# mikrophonie_2023.net
KiCad netlist of a schematic drawn in EAGLE
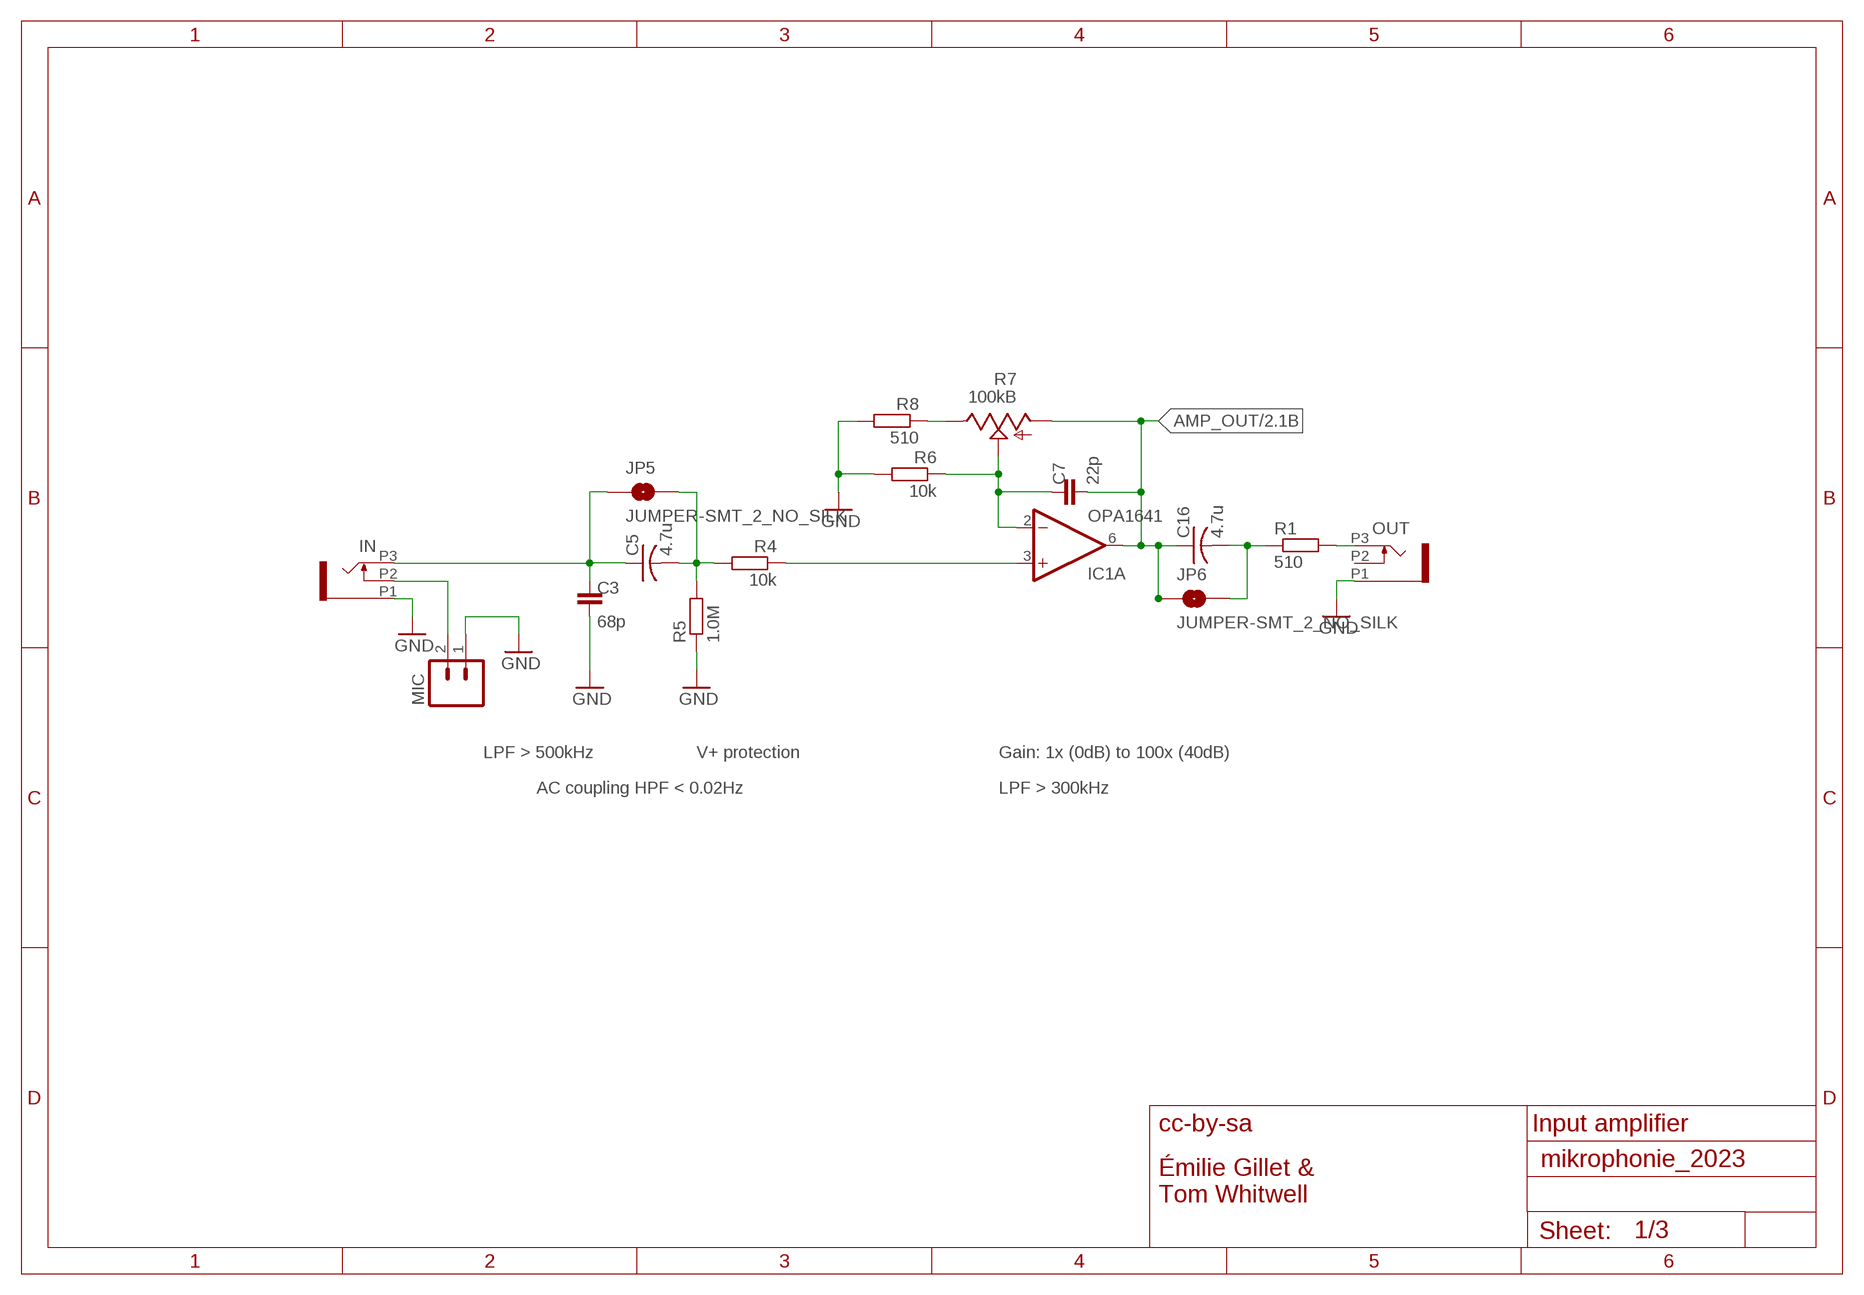
[diagram p0: schematic, sheet 1]
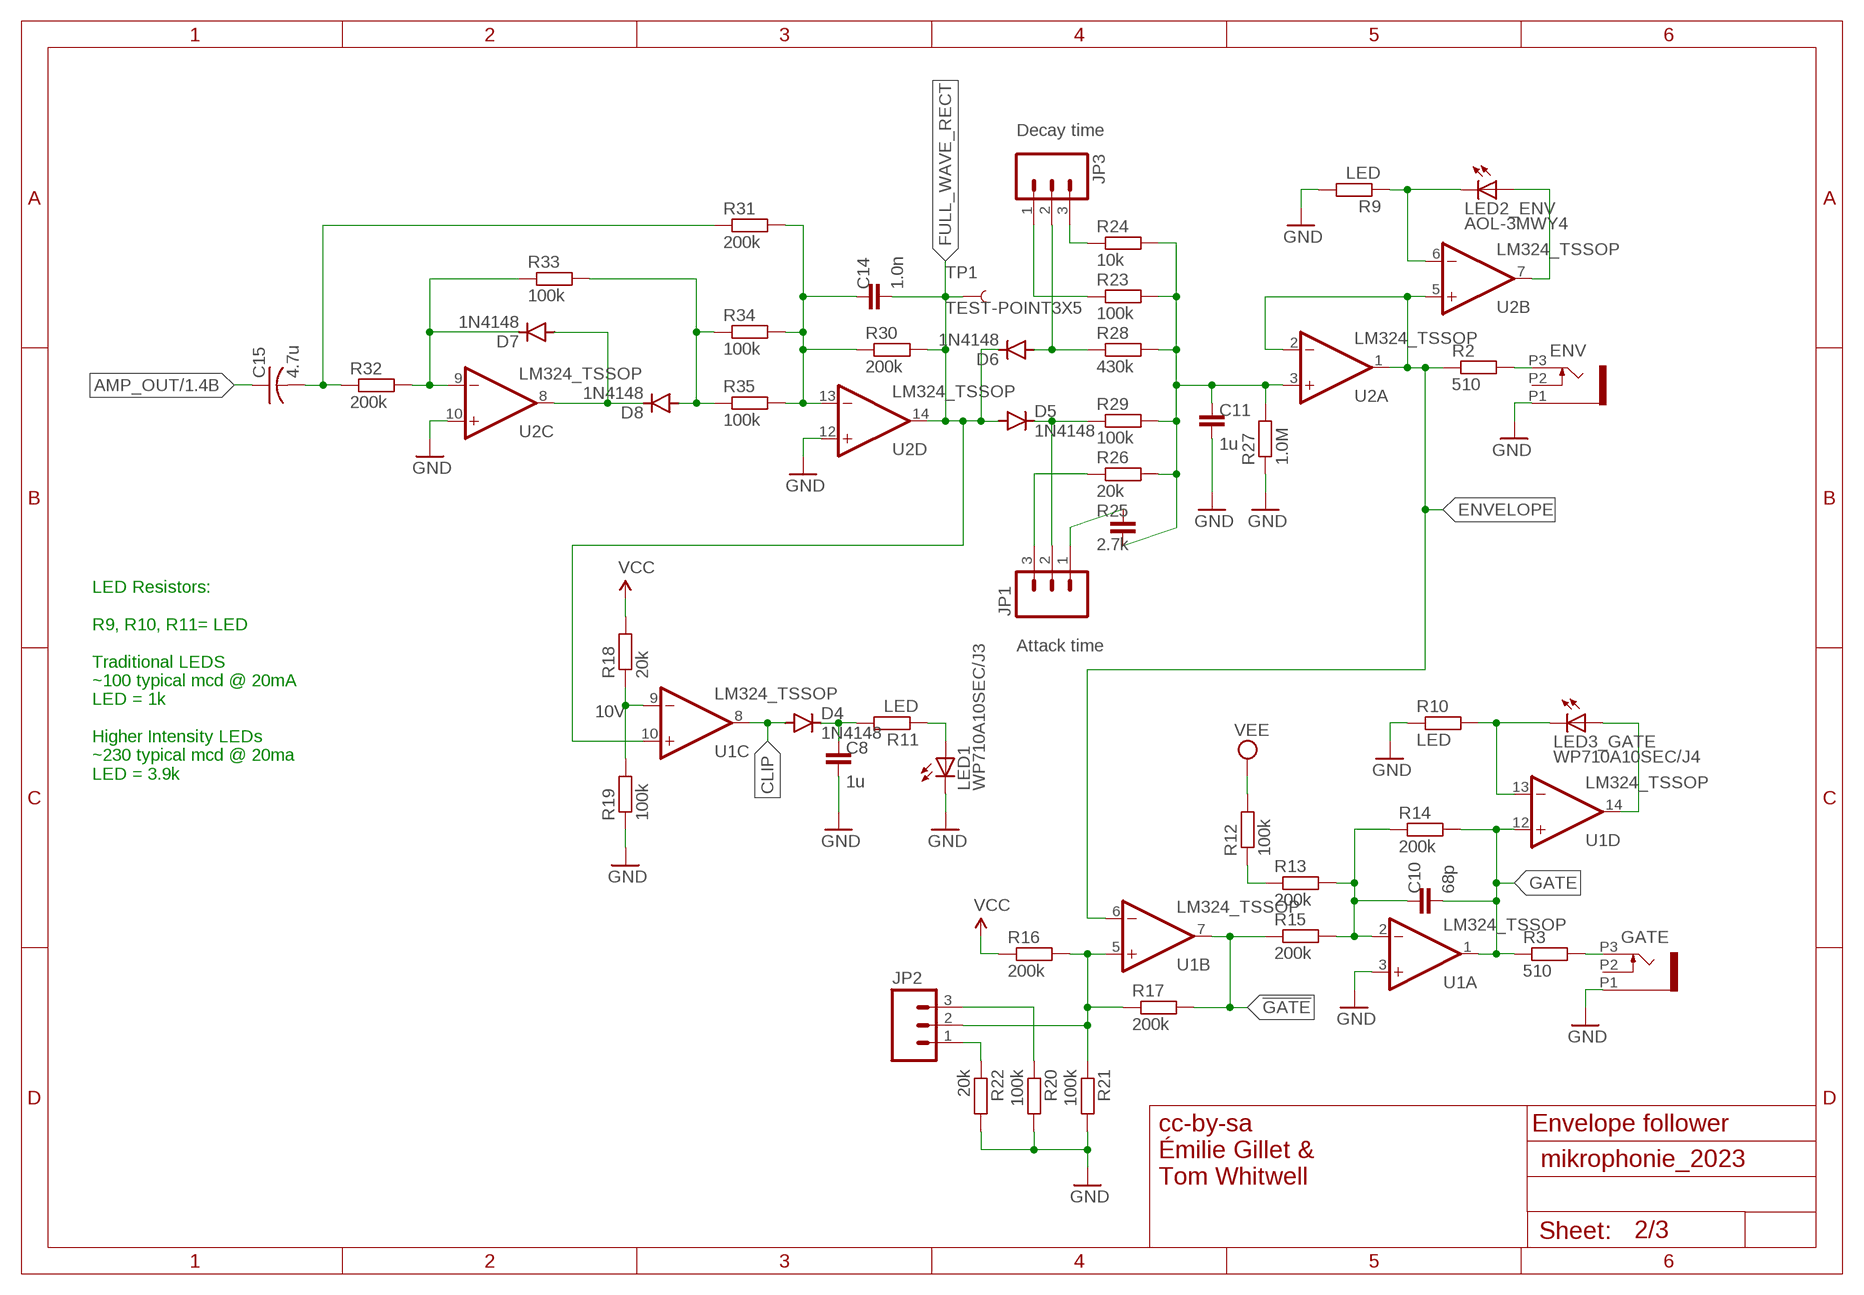
[diagram p1: schematic, sheet 2]
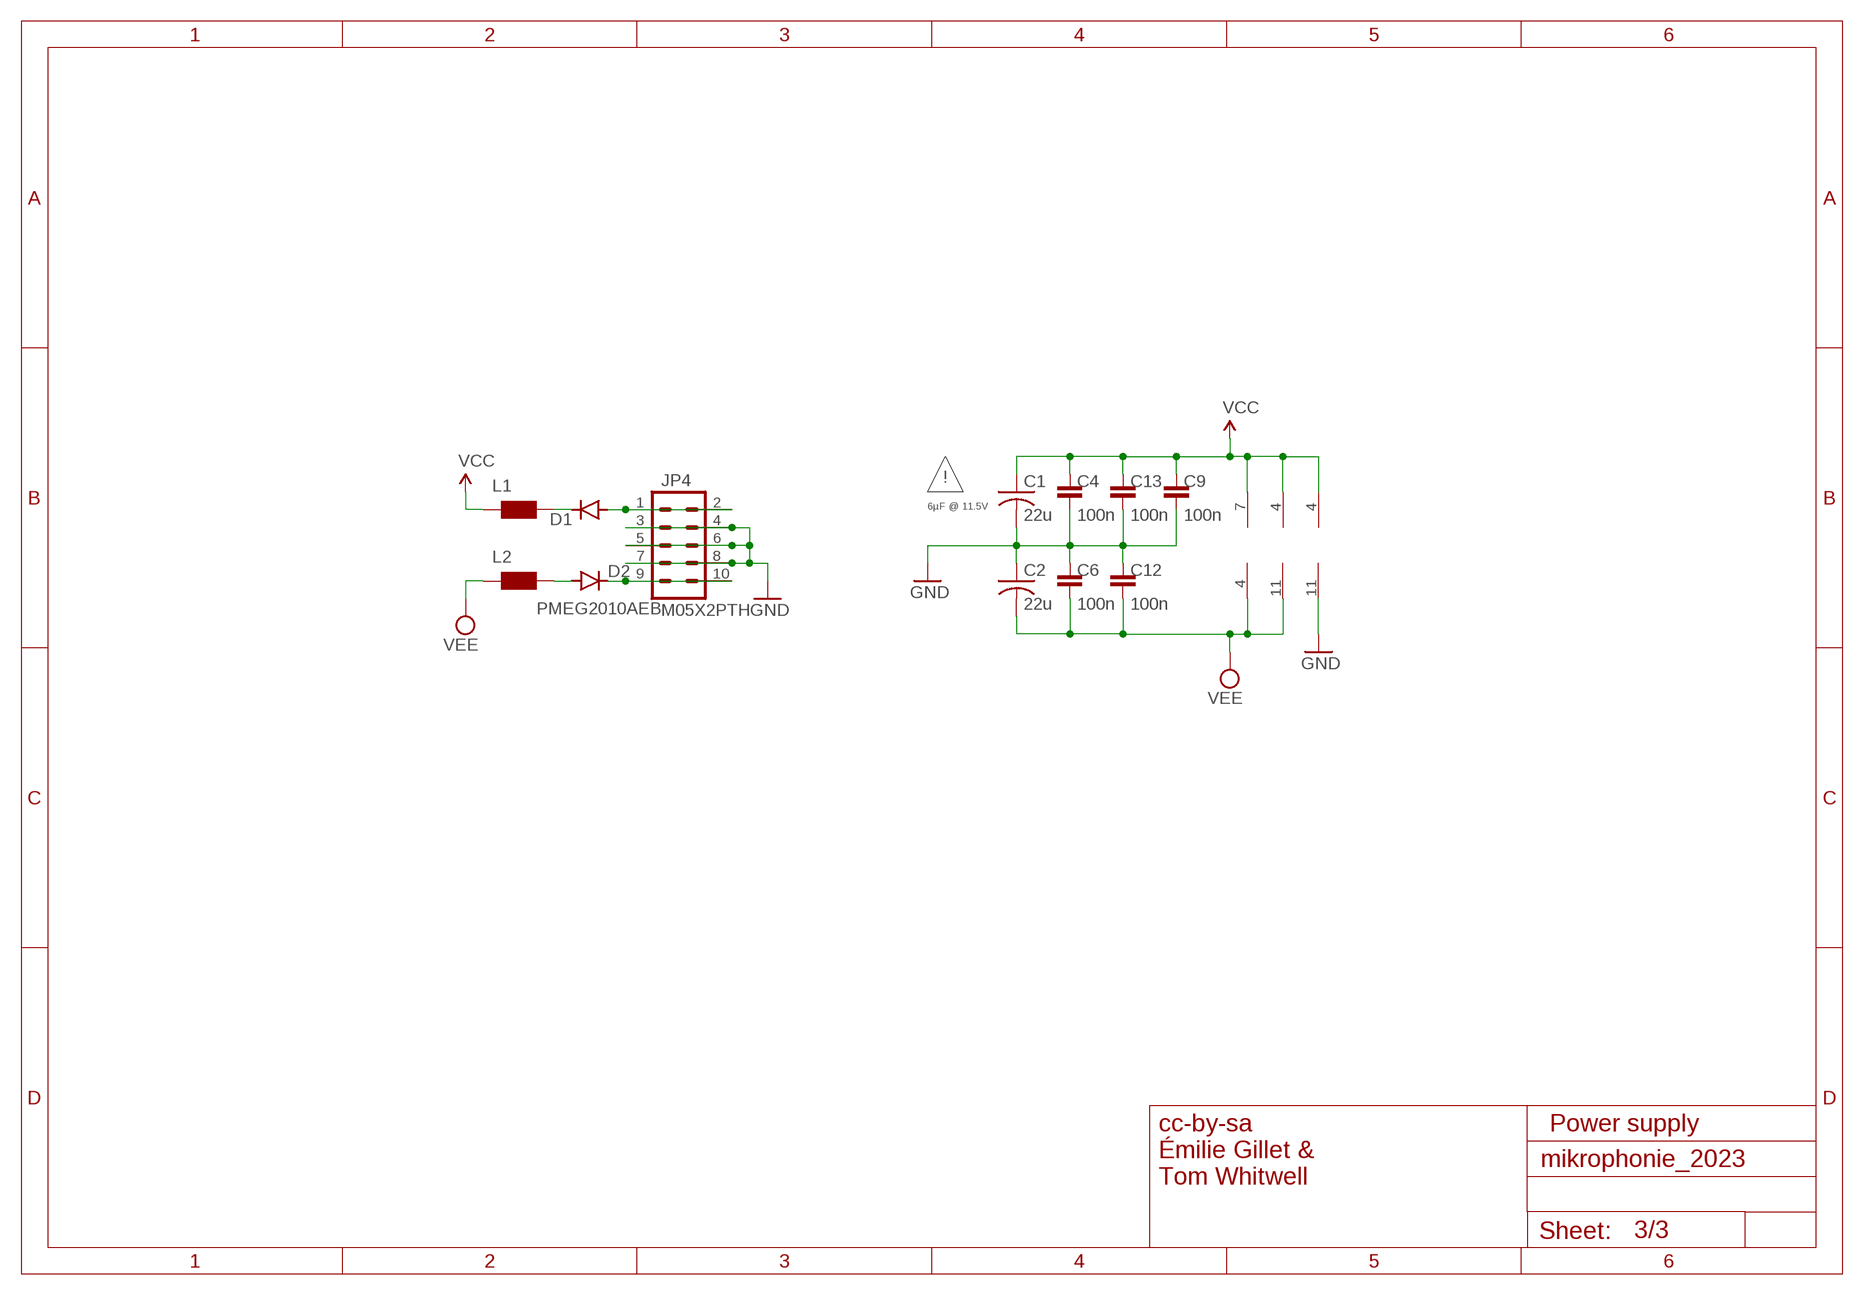
[diagram p2: schematic, sheet 3]

(export (version "E")
  (design (tool "Eeschema 10.0.6"))
  (components
    (comp (ref "C8")
      (value "1u")
      (footprint "eagle-import:C0402-90")
      (libsource (lib "eagle-import") (part "CAPACITOR-90"))
    )
    (comp (ref "C10")
      (value "68p")
      (footprint "eagle-import:C0402-90")
      (libsource (lib "eagle-import") (part "CAPACITOR-90"))
    )
    (comp (ref "C11")
      (value "1u")
      (footprint "eagle-import:C0402-90")
      (libsource (lib "eagle-import") (part "CAPACITOR-90"))
    )
    (comp (ref "C14")
      (value "1.0n")
      (footprint "eagle-import:C0402-90")
      (libsource (lib "eagle-import") (part "CAPACITOR-90"))
    )
    (comp (ref "C15")
      (value "4.7u")
      (footprint "eagle-import:C0603")
      (libsource (lib "eagle-import") (part "C-USC0603"))
    )
    (comp (ref "D4")
      (value "1N4148")
      (footprint "eagle-import:SOD523")
      (libsource (lib "eagle-import") (part "DIODE-SOD523"))
    )
    (comp (ref "D5")
      (value "1N4148")
      (footprint "eagle-import:SOD523")
      (libsource (lib "eagle-import") (part "DIODE-SOD523"))
    )
    (comp (ref "D6")
      (value "1N4148")
      (footprint "eagle-import:SOD523")
      (libsource (lib "eagle-import") (part "DIODE-SOD523"))
    )
    (comp (ref "D7")
      (value "1N4148")
      (footprint "eagle-import:SOD523")
      (libsource (lib "eagle-import") (part "DIODE-SOD523"))
    )
    (comp (ref "D8")
      (value "1N4148")
      (footprint "eagle-import:SOD523")
      (libsource (lib "eagle-import") (part "DIODE-SOD523"))
    )
    (comp (ref "ENV")
      (value "PJ301_THONKICONN6")
      (footprint "eagle-import:WQP_PJ_301M6")
      (libsource (lib "eagle-import") (part "PJ301_THONKICONN6"))
    )
    (comp (ref "GATE")
      (value "PJ301_THONKICONN6")
      (footprint "eagle-import:WQP_PJ_301M6")
      (libsource (lib "eagle-import") (part "PJ301_THONKICONN6"))
    )
    (comp (ref "JP1")
      (value "M03PTH")
      (footprint "eagle-import:1X03")
      (libsource (lib "eagle-import") (part "M03PTH"))
    )
    (comp (ref "JP2")
      (value "M03PTH")
      (footprint "eagle-import:1X03")
      (libsource (lib "eagle-import") (part "M03PTH"))
    )
    (comp (ref "JP3")
      (value "M03PTH")
      (footprint "eagle-import:1X03")
      (libsource (lib "eagle-import") (part "M03PTH"))
    )
    (comp (ref "LED1")
      (value "WP710A10SEC/J3")
      (footprint "eagle-import:LED3MM")
      (libsource (lib "eagle-import") (part "LED3MM"))
    )
    (comp (ref "LED2_ENV")
      (value "AOL-3MWY4")
      (footprint "eagle-import:LED3MM")
      (libsource (lib "eagle-import") (part "LED3MM"))
    )
    (comp (ref "LED3_GATE")
      (value "WP710A10SEC/J4")
      (footprint "eagle-import:LED3MM")
      (libsource (lib "eagle-import") (part "LED3MM"))
    )
    (comp (ref "R2")
      (value "510")
      (footprint "eagle-import:C0402-90")
      (libsource (lib "eagle-import") (part "RESISTOR-0402_90"))
    )
    (comp (ref "R3")
      (value "510")
      (footprint "eagle-import:C0402-90")
      (libsource (lib "eagle-import") (part "RESISTOR-0402_90"))
    )
    (comp (ref "R9")
      (value "LED")
      (footprint "eagle-import:C0402-90")
      (libsource (lib "eagle-import") (part "RESISTOR-0402_90"))
    )
    (comp (ref "R10")
      (value "LED")
      (footprint "eagle-import:C0402-90")
      (libsource (lib "eagle-import") (part "RESISTOR-0402_90"))
    )
    (comp (ref "R11")
      (value "LED")
      (footprint "eagle-import:C0402-90")
      (libsource (lib "eagle-import") (part "RESISTOR-0402_90"))
    )
    (comp (ref "R12")
      (value "100k")
      (footprint "eagle-import:C0402-90")
      (libsource (lib "eagle-import") (part "RESISTOR-0402_90"))
    )
    (comp (ref "R13")
      (value "200k")
      (footprint "eagle-import:C0402-90")
      (libsource (lib "eagle-import") (part "RESISTOR-0402_90"))
    )
    (comp (ref "R14")
      (value "200k")
      (footprint "eagle-import:C0402-90")
      (libsource (lib "eagle-import") (part "RESISTOR-0402_90"))
    )
    (comp (ref "R15")
      (value "200k")
      (footprint "eagle-import:C0402-90")
      (libsource (lib "eagle-import") (part "RESISTOR-0402_90"))
    )
    (comp (ref "R16")
      (value "200k")
      (footprint "eagle-import:C0402-90")
      (libsource (lib "eagle-import") (part "RESISTOR-0402_90"))
    )
    (comp (ref "R17")
      (value "200k")
      (footprint "eagle-import:C0402-90")
      (libsource (lib "eagle-import") (part "RESISTOR-0402_90"))
    )
    (comp (ref "R18")
      (value "20k")
      (footprint "eagle-import:C0402-90")
      (libsource (lib "eagle-import") (part "RESISTOR-0402_90"))
    )
    (comp (ref "R19")
      (value "100k")
      (footprint "eagle-import:C0402-90")
      (libsource (lib "eagle-import") (part "RESISTOR-0402_90"))
    )
    (comp (ref "R20")
      (value "100k")
      (footprint "eagle-import:C0402-90")
      (libsource (lib "eagle-import") (part "RESISTOR-0402_90"))
    )
    (comp (ref "R21")
      (value "100k")
      (footprint "eagle-import:C0402-90")
      (libsource (lib "eagle-import") (part "RESISTOR-0402_90"))
    )
    (comp (ref "R22")
      (value "20k")
      (footprint "eagle-import:C0402-90")
      (libsource (lib "eagle-import") (part "RESISTOR-0402_90"))
    )
    (comp (ref "R23")
      (value "100k")
      (footprint "eagle-import:C0402-90")
      (libsource (lib "eagle-import") (part "RESISTOR-0402_90"))
    )
    (comp (ref "R24")
      (value "10k")
      (footprint "eagle-import:C0402-90")
      (libsource (lib "eagle-import") (part "RESISTOR-0402_90"))
    )
    (comp (ref "R25")
      (value "2.7k")
      (footprint "eagle-import:C0402-90")
      (libsource (lib "eagle-import") (part "CAPACITOR-90"))
    )
    (comp (ref "R26")
      (value "20k")
      (footprint "eagle-import:C0402-90")
      (libsource (lib "eagle-import") (part "RESISTOR-0402_90"))
    )
    (comp (ref "R27")
      (value "1.0M")
      (footprint "eagle-import:C0402-90")
      (libsource (lib "eagle-import") (part "RESISTOR-0402_90"))
    )
    (comp (ref "R28")
      (value "430k")
      (footprint "eagle-import:C0402-90")
      (libsource (lib "eagle-import") (part "RESISTOR-0402_90"))
    )
    (comp (ref "R29")
      (value "100k")
      (footprint "eagle-import:C0402-90")
      (libsource (lib "eagle-import") (part "RESISTOR-0402_90"))
    )
    (comp (ref "R30")
      (value "200k")
      (footprint "eagle-import:C0402-90")
      (libsource (lib "eagle-import") (part "RESISTOR-0402_90"))
    )
    (comp (ref "R31")
      (value "200k")
      (footprint "eagle-import:C0402-90")
      (libsource (lib "eagle-import") (part "RESISTOR-0402_90"))
    )
    (comp (ref "R32")
      (value "200k")
      (footprint "eagle-import:C0402-90")
      (libsource (lib "eagle-import") (part "RESISTOR-0402_90"))
    )
    (comp (ref "R33")
      (value "100k")
      (footprint "eagle-import:C0402-90")
      (libsource (lib "eagle-import") (part "RESISTOR-0402_90"))
    )
    (comp (ref "R34")
      (value "100k")
      (footprint "eagle-import:C0402-90")
      (libsource (lib "eagle-import") (part "RESISTOR-0402_90"))
    )
    (comp (ref "R35")
      (value "100k")
      (footprint "eagle-import:C0402-90")
      (libsource (lib "eagle-import") (part "RESISTOR-0402_90"))
    )
    (comp (ref "TP1")
      (value "TEST-POINT3X5")
      (footprint "eagle-import:PAD.03X.05")
      (libsource (lib "eagle-import") (part "TEST-POINT3X5"))
    )
    (comp (ref "U1")
      (value "LM324_TSSOP")
      (footprint "eagle-import:SOP65P640X120-14N")
      (fields (field (name "MPN") "MCP6004-I/ST"))
      (libsource (lib "eagle-import") (part "LM324_TSSOP"))
    )
    (comp (ref "U2")
      (value "LM324_TSSOP")
      (footprint "eagle-import:SOP65P640X120-14N")
      (fields (field (name "MPN") "MCP6004-I/ST"))
      (libsource (lib "eagle-import") (part "LM324_TSSOP"))
    )
    (comp (ref "C1")
      (value "22u")
      (footprint "eagle-import:C1206")
      (libsource (lib "eagle-import") (part "C-USC1206"))
    )
    (comp (ref "C2")
      (value "22u")
      (footprint "eagle-import:C1206")
      (libsource (lib "eagle-import") (part "C-USC1206"))
    )
    (comp (ref "C4")
      (value "100n")
      (footprint "eagle-import:C0402-90")
      (libsource (lib "eagle-import") (part "CAPACITOR-90"))
    )
    (comp (ref "C6")
      (value "100n")
      (footprint "eagle-import:C0402-90")
      (libsource (lib "eagle-import") (part "CAPACITOR-90"))
    )
    (comp (ref "C9")
      (value "100n")
      (footprint "eagle-import:C0402-90")
      (libsource (lib "eagle-import") (part "CAPACITOR-90"))
    )
    (comp (ref "C12")
      (value "100n")
      (footprint "eagle-import:C0402-90")
      (libsource (lib "eagle-import") (part "CAPACITOR-90"))
    )
    (comp (ref "C13")
      (value "100n")
      (footprint "eagle-import:C0402-90")
      (libsource (lib "eagle-import") (part "CAPACITOR-90"))
    )
    (comp (ref "D1")
      (value "PMEG2010AEB")
      (footprint "eagle-import:SOD523")
      (libsource (lib "eagle-import") (part "DIODE-SOD523"))
    )
    (comp (ref "D2")
      (value "PMEG2010AEB")
      (footprint "eagle-import:SOD523")
      (libsource (lib "eagle-import") (part "DIODE-SOD523"))
    )
    (comp (ref "IC1")
      (value "OPA1641")
      (footprint "eagle-import:MSOP8")
      (libsource (lib "eagle-import") (part "OPA1641"))
    )
    (comp (ref "JP4")
      (value "M05X2PTH")
      (footprint "eagle-import:AVR_ICSP")
      (libsource (lib "eagle-import") (part "M05X2PTH"))
    )
    (comp (ref "L1")
      (value "WE-CBF_0603")
      (footprint "eagle-import:0603")
      (libsource (lib "eagle-import") (part "WE-CBF_0603"))
    )
    (comp (ref "L2")
      (value "WE-CBF_0603")
      (footprint "eagle-import:0603")
      (libsource (lib "eagle-import") (part "WE-CBF_0603"))
    )
    (comp (ref "C3")
      (value "68p")
      (footprint "eagle-import:C0402-90")
      (libsource (lib "eagle-import") (part "CAPACITOR-90"))
    )
    (comp (ref "C5")
      (value "4.7u")
      (footprint "eagle-import:C0603")
      (libsource (lib "eagle-import") (part "C-USC0603"))
    )
    (comp (ref "C7")
      (value "22p")
      (footprint "eagle-import:C0402-90")
      (libsource (lib "eagle-import") (part "CAPACITOR-90"))
    )
    (comp (ref "C16")
      (value "4.7u")
      (footprint "eagle-import:C0603")
      (libsource (lib "eagle-import") (part "C-USC0603"))
    )
    (comp (ref "IN")
      (value "PJ301_THONKICONN6")
      (footprint "eagle-import:WQP_PJ_301M6")
      (libsource (lib "eagle-import") (part "PJ301_THONKICONN6"))
    )
    (comp (ref "JP5")
      (value "JUMPER-SMT_2_NO_SILK")
      (footprint "eagle-import:SMT-JUMPER_2_NO_SILK")
      (libsource (lib "eagle-import") (part "JUMPER-SMT_2_NO_SILK"))
    )
    (comp (ref "JP6")
      (value "JUMPER-SMT_2_NO_SILK")
      (footprint "eagle-import:SMT-JUMPER_2_NO_SILK")
      (libsource (lib "eagle-import") (part "JUMPER-SMT_2_NO_SILK"))
    )
    (comp (ref "MIC")
      (value "M02TINY")
      (footprint "eagle-import:1X02_TINY")
      (libsource (lib "eagle-import") (part "M02TINY"))
    )
    (comp (ref "OUT")
      (value "PJ301_THONKICONN6")
      (footprint "eagle-import:WQP_PJ_301M6")
      (libsource (lib "eagle-import") (part "PJ301_THONKICONN6"))
    )
    (comp (ref "R1")
      (value "510")
      (footprint "eagle-import:C0402-90")
      (libsource (lib "eagle-import") (part "RESISTOR-0402_90"))
    )
    (comp (ref "R4")
      (value "10k")
      (footprint "eagle-import:C0402-90")
      (libsource (lib "eagle-import") (part "RESISTOR-0402_90"))
    )
    (comp (ref "R5")
      (value "1.0M")
      (footprint "eagle-import:C0402-90")
      (libsource (lib "eagle-import") (part "RESISTOR-0402_90"))
    )
    (comp (ref "R6")
      (value "10k")
      (footprint "eagle-import:C0402-90")
      (libsource (lib "eagle-import") (part "RESISTOR-0402_90"))
    )
    (comp (ref "R7")
      (value "100kB")
      (footprint "eagle-import:ALPS_POT_VERTICAL_PS")
      (libsource (lib "eagle-import") (part "POT_USVERTICAL_PS"))
    )
    (comp (ref "R8")
      (value "510")
      (footprint "eagle-import:C0402-90")
      (libsource (lib "eagle-import") (part "RESISTOR-0402_90"))
    )
  )
  (nets
    (net (code "1") (name "AMP_OUT") (class "Default")
      (node (ref "C15") (pin "1") (pinfunction "1_1") (pintype "passive"))
      (node (ref "C16") (pin "1") (pinfunction "1_1") (pintype "passive"))
      (node (ref "C7") (pin "2") (pinfunction "2_2") (pintype "passive"))
      (node (ref "IC1") (pin "6") (pinfunction "OUT_6") (pintype "output"))
      (node (ref "JP6") (pin "1") (pinfunction "1_1") (pintype "passive"))
      (node (ref "R7") (pin "P$3") (pinfunction "A_P$3") (pintype "passive"))
    )
    (net (code "2") (name "CLIP") (class "Default")
      (node (ref "D4") (pin "A") (pinfunction "A_A") (pintype "passive"))
      (node (ref "U1") (pin "8") (pinfunction "OUT_8") (pintype "output"))
    )
    (net (code "3") (name "ENVELOPE") (class "Default")
      (node (ref "R2") (pin "1") (pinfunction "1_1") (pintype "passive"))
      (node (ref "U1") (pin "6") (pinfunction "-IN_6") (pintype "input"))
      (node (ref "U2") (pin "1") (pinfunction "OUT_1") (pintype "output"))
      (node (ref "U2") (pin "2") (pinfunction "-IN_2") (pintype "input"))
      (node (ref "U2") (pin "5") (pinfunction "+IN_5") (pintype "input"))
    )
    (net (code "4") (name "FULL_WAVE_RECT") (class "Default")
      (node (ref "C14") (pin "2") (pinfunction "2_2") (pintype "passive"))
      (node (ref "D5") (pin "A") (pinfunction "A_A") (pintype "passive"))
      (node (ref "D6") (pin "C") (pinfunction "C_C") (pintype "passive"))
      (node (ref "R30") (pin "2") (pinfunction "2_2") (pintype "passive"))
      (node (ref "TP1") (pin "P$1") (pinfunction "1_P$1") (pintype "bidirectional"))
      (node (ref "U1") (pin "10") (pinfunction "+IN_10") (pintype "input"))
      (node (ref "U2") (pin "14") (pinfunction "OUT_14") (pintype "output"))
    )
    (net (code "5") (name "GATE") (class "Default")
      (node (ref "C10") (pin "2") (pinfunction "2_2") (pintype "passive"))
      (node (ref "R14") (pin "2") (pinfunction "2_2") (pintype "passive"))
      (node (ref "R3") (pin "1") (pinfunction "1_1") (pintype "passive"))
      (node (ref "U1") (pin "1") (pinfunction "OUT_1") (pintype "output"))
      (node (ref "U1") (pin "12") (pinfunction "+IN_12") (pintype "input"))
    )
    (net (code "6") (name "GND") (class "Default")
      (node (ref "C1") (pin "2") (pinfunction "2_2") (pintype "passive"))
      (node (ref "C11") (pin "2") (pinfunction "2_2") (pintype "passive"))
      (node (ref "C12") (pin "1") (pinfunction "1_1") (pintype "passive"))
      (node (ref "C13") (pin "2") (pinfunction "2_2") (pintype "passive"))
      (node (ref "C2") (pin "1") (pinfunction "1_1") (pintype "passive"))
      (node (ref "C3") (pin "2") (pinfunction "2_2") (pintype "passive"))
      (node (ref "C4") (pin "2") (pinfunction "2_2") (pintype "passive"))
      (node (ref "C6") (pin "1") (pinfunction "1_1") (pintype "passive"))
      (node (ref "C8") (pin "2") (pinfunction "2_2") (pintype "passive"))
      (node (ref "C9") (pin "2") (pinfunction "2_2") (pintype "passive"))
      (node (ref "ENV") (pin "P1") (pinfunction "1_P1") (pintype "passive"))
      (node (ref "GATE") (pin "P1") (pinfunction "1_P1") (pintype "passive"))
      (node (ref "IN") (pin "P1") (pinfunction "1_P1") (pintype "passive"))
      (node (ref "JP4") (pin "3") (pinfunction "3_3") (pintype "passive"))
      (node (ref "JP4") (pin "4") (pinfunction "4_4") (pintype "passive"))
      (node (ref "JP4") (pin "5") (pinfunction "5_5") (pintype "passive"))
      (node (ref "JP4") (pin "6") (pinfunction "6_6") (pintype "passive"))
      (node (ref "JP4") (pin "7") (pinfunction "7_7") (pintype "passive"))
      (node (ref "JP4") (pin "8") (pinfunction "8_8") (pintype "passive"))
      (node (ref "LED1") (pin "K") (pinfunction "C_K") (pintype "passive"))
      (node (ref "MIC") (pin "1") (pinfunction "1_1") (pintype "passive"))
      (node (ref "OUT") (pin "P1") (pinfunction "1_P1") (pintype "passive"))
      (node (ref "R10") (pin "1") (pinfunction "1_1") (pintype "passive"))
      (node (ref "R19") (pin "1") (pinfunction "1_1") (pintype "passive"))
      (node (ref "R20") (pin "2") (pinfunction "2_2") (pintype "passive"))
      (node (ref "R21") (pin "2") (pinfunction "2_2") (pintype "passive"))
      (node (ref "R22") (pin "2") (pinfunction "2_2") (pintype "passive"))
      (node (ref "R27") (pin "1") (pinfunction "1_1") (pintype "passive"))
      (node (ref "R5") (pin "1") (pinfunction "1_1") (pintype "passive"))
      (node (ref "R6") (pin "2") (pinfunction "2_2") (pintype "passive"))
      (node (ref "R8") (pin "2") (pinfunction "2_2") (pintype "passive"))
      (node (ref "R9") (pin "2") (pinfunction "2_2") (pintype "passive"))
      (node (ref "U1") (pin "11") (pinfunction "V-_11") (pintype "power_in"))
      (node (ref "U1") (pin "3") (pinfunction "+IN_3") (pintype "input"))
      (node (ref "U2") (pin "10") (pinfunction "+IN_10") (pintype "input"))
      (node (ref "U2") (pin "12") (pinfunction "+IN_12") (pintype "input"))
    )
    (net (code "7") (name "Net-(C5-Pad2)") (class "Default")
      (node (ref "C5") (pin "2") (pinfunction "2_2") (pintype "passive"))
      (node (ref "JP5") (pin "2") (pinfunction "2_2") (pintype "passive"))
      (node (ref "R4") (pin "2") (pinfunction "2_2") (pintype "passive"))
      (node (ref "R5") (pin "2") (pinfunction "2_2") (pintype "passive"))
    )
    (net (code "8") (name "Net-(C8-Pad1)") (class "Default")
      (node (ref "C8") (pin "1") (pinfunction "1_1") (pintype "passive"))
      (node (ref "D4") (pin "C") (pinfunction "C_C") (pintype "passive"))
      (node (ref "R11") (pin "2") (pinfunction "2_2") (pintype "passive"))
    )
    (net (code "9") (name "Net-(C15-Pad2)") (class "Default")
      (node (ref "C15") (pin "2") (pinfunction "2_2") (pintype "passive"))
      (node (ref "R31") (pin "1") (pinfunction "1_1") (pintype "passive"))
      (node (ref "R32") (pin "1") (pinfunction "1_1") (pintype "passive"))
    )
    (net (code "10") (name "Net-(C16-Pad2)") (class "Default")
      (node (ref "C16") (pin "2") (pinfunction "2_2") (pintype "passive"))
      (node (ref "JP6") (pin "2") (pinfunction "2_2") (pintype "passive"))
      (node (ref "R1") (pin "1") (pinfunction "1_1") (pintype "passive"))
    )
    (net (code "11") (name "Net-(D1-PadA)") (class "Default")
      (node (ref "D1") (pin "A") (pinfunction "A_A") (pintype "passive"))
      (node (ref "JP4") (pin "1") (pinfunction "1_1") (pintype "passive"))
      (node (ref "JP4") (pin "2") (pinfunction "2_2") (pintype "passive"))
    )
    (net (code "12") (name "Net-(D1-PadC)") (class "Default")
      (node (ref "D1") (pin "C") (pinfunction "C_C") (pintype "passive"))
      (node (ref "L1") (pin "2") (pinfunction "2_2") (pintype "passive"))
    )
    (net (code "13") (name "Net-(D2-PadA)") (class "Default")
      (node (ref "D2") (pin "A") (pinfunction "A_A") (pintype "passive"))
      (node (ref "L2") (pin "2") (pinfunction "2_2") (pintype "passive"))
    )
    (net (code "14") (name "Net-(D2-PadC)") (class "Default")
      (node (ref "D2") (pin "C") (pinfunction "C_C") (pintype "passive"))
      (node (ref "JP4") (pin "10") (pinfunction "10_10") (pintype "passive"))
      (node (ref "JP4") (pin "9") (pinfunction "9_9") (pintype "passive"))
    )
    (net (code "15") (name "Net-(D5-PadC)") (class "Default")
      (node (ref "D5") (pin "C") (pinfunction "C_C") (pintype "passive"))
      (node (ref "JP1") (pin "2") (pinfunction "2_2") (pintype "passive"))
      (node (ref "R29") (pin "1") (pinfunction "1_1") (pintype "passive"))
    )
    (net (code "16") (name "Net-(D6-PadA)") (class "Default")
      (node (ref "D6") (pin "A") (pinfunction "A_A") (pintype "passive"))
      (node (ref "JP3") (pin "2") (pinfunction "2_2") (pintype "passive"))
      (node (ref "R28") (pin "1") (pinfunction "1_1") (pintype "passive"))
    )
    (net (code "17") (name "Net-(D8-PadA)") (class "Default")
      (node (ref "D8") (pin "A") (pinfunction "A_A") (pintype "passive"))
      (node (ref "R33") (pin "2") (pinfunction "2_2") (pintype "passive"))
      (node (ref "R34") (pin "1") (pinfunction "1_1") (pintype "passive"))
      (node (ref "R35") (pin "1") (pinfunction "1_1") (pintype "passive"))
    )
    (net (code "18") (name "Net-(ENV-3)") (class "Default")
      (node (ref "ENV") (pin "P3") (pinfunction "3_P3") (pintype "passive"))
      (node (ref "R2") (pin "2") (pinfunction "2_2") (pintype "passive"))
    )
    (net (code "19") (name "Net-(GATE-3)") (class "Default")
      (node (ref "GATE") (pin "P3") (pinfunction "3_P3") (pintype "passive"))
      (node (ref "R3") (pin "2") (pinfunction "2_2") (pintype "passive"))
    )
    (net (code "20") (name "Net-(IC1A-+IN)") (class "Default")
      (node (ref "IC1") (pin "3") (pinfunction "+IN_3") (pintype "input"))
      (node (ref "R4") (pin "1") (pinfunction "1_1") (pintype "passive"))
    )
    (net (code "21") (name "Net-(IC1A--IN)") (class "Default")
      (node (ref "C7") (pin "1") (pinfunction "1_1") (pintype "passive"))
      (node (ref "IC1") (pin "2") (pinfunction "-IN_2") (pintype "input"))
      (node (ref "R6") (pin "1") (pinfunction "1_1") (pintype "passive"))
      (node (ref "R7") (pin "P$2") (pinfunction "S_P$2") (pintype "passive"))
    )
    (net (code "22") (name "Net-(IN-2)") (class "Default")
      (node (ref "IN") (pin "P2") (pinfunction "2_P2") (pintype "passive"))
      (node (ref "MIC") (pin "2") (pinfunction "2_2") (pintype "passive"))
    )
    (net (code "23") (name "Net-(IN-3)") (class "Default")
      (node (ref "C3") (pin "1") (pinfunction "1_1") (pintype "passive"))
      (node (ref "C5") (pin "1") (pinfunction "1_1") (pintype "passive"))
      (node (ref "IN") (pin "P3") (pinfunction "3_P3") (pintype "passive"))
      (node (ref "JP5") (pin "1") (pinfunction "1_1") (pintype "passive"))
    )
    (net (code "24") (name "Net-(JP1-Pad1)") (class "Default")
      (node (ref "JP1") (pin "1") (pinfunction "1_1") (pintype "passive"))
      (node (ref "R25") (pin "1") (pinfunction "1_1") (pintype "passive"))
    )
    (net (code "25") (name "Net-(JP1-Pad3)") (class "Default")
      (node (ref "JP1") (pin "3") (pinfunction "3_3") (pintype "passive"))
      (node (ref "R26") (pin "1") (pinfunction "1_1") (pintype "passive"))
    )
    (net (code "26") (name "Net-(JP2-Pad1)") (class "Default")
      (node (ref "JP2") (pin "1") (pinfunction "1_1") (pintype "passive"))
      (node (ref "R22") (pin "1") (pinfunction "1_1") (pintype "passive"))
    )
    (net (code "27") (name "Net-(JP2-Pad3)") (class "Default")
      (node (ref "JP2") (pin "3") (pinfunction "3_3") (pintype "passive"))
      (node (ref "R20") (pin "1") (pinfunction "1_1") (pintype "passive"))
    )
    (net (code "28") (name "Net-(JP3-Pad1)") (class "Default")
      (node (ref "JP3") (pin "1") (pinfunction "1_1") (pintype "passive"))
      (node (ref "R23") (pin "1") (pinfunction "1_1") (pintype "passive"))
    )
    (net (code "29") (name "Net-(JP3-Pad3)") (class "Default")
      (node (ref "JP3") (pin "3") (pinfunction "3_3") (pintype "passive"))
      (node (ref "R24") (pin "1") (pinfunction "1_1") (pintype "passive"))
    )
    (net (code "30") (name "Net-(LED1-PadA)") (class "Default")
      (node (ref "LED1") (pin "A") (pinfunction "A_A") (pintype "passive"))
      (node (ref "R11") (pin "1") (pinfunction "1_1") (pintype "passive"))
    )
    (net (code "31") (name "Net-(LED2_ENV-C)") (class "Default")
      (node (ref "LED2_ENV") (pin "K") (pinfunction "C_K") (pintype "passive"))
      (node (ref "R9") (pin "1") (pinfunction "1_1") (pintype "passive"))
      (node (ref "U2") (pin "6") (pinfunction "-IN_6") (pintype "input"))
    )
    (net (code "32") (name "Net-(LED3_GATE-C)") (class "Default")
      (node (ref "LED3_GATE") (pin "K") (pinfunction "C_K") (pintype "passive"))
      (node (ref "R10") (pin "2") (pinfunction "2_2") (pintype "passive"))
      (node (ref "U1") (pin "13") (pinfunction "-IN_13") (pintype "input"))
    )
    (net (code "33") (name "Net-(OUT-3)") (class "Default")
      (node (ref "OUT") (pin "P3") (pinfunction "3_P3") (pintype "passive"))
      (node (ref "R1") (pin "2") (pinfunction "2_2") (pintype "passive"))
    )
    (net (code "34") (name "Net-(R7-E)") (class "Default")
      (node (ref "R7") (pin "P$1") (pinfunction "E_P$1") (pintype "passive"))
      (node (ref "R8") (pin "1") (pinfunction "1_1") (pintype "passive"))
    )
    (net (code "35") (name "Net-(R12-Pad1)") (class "Default")
      (node (ref "R12") (pin "1") (pinfunction "1_1") (pintype "passive"))
      (node (ref "R13") (pin "1") (pinfunction "1_1") (pintype "passive"))
    )
    (net (code "36") (name "Net-(U1A--IN)") (class "Default")
      (node (ref "C10") (pin "1") (pinfunction "1_1") (pintype "passive"))
      (node (ref "R13") (pin "2") (pinfunction "2_2") (pintype "passive"))
      (node (ref "R14") (pin "1") (pinfunction "1_1") (pintype "passive"))
      (node (ref "R15") (pin "2") (pinfunction "2_2") (pintype "passive"))
      (node (ref "U1") (pin "2") (pinfunction "-IN_2") (pintype "input"))
    )
    (net (code "37") (name "Net-(U1B-+IN)") (class "Default")
      (node (ref "JP2") (pin "2") (pinfunction "2_2") (pintype "passive"))
      (node (ref "R16") (pin "2") (pinfunction "2_2") (pintype "passive"))
      (node (ref "R17") (pin "1") (pinfunction "1_1") (pintype "passive"))
      (node (ref "R21") (pin "1") (pinfunction "1_1") (pintype "passive"))
      (node (ref "U1") (pin "5") (pinfunction "+IN_5") (pintype "input"))
    )
    (net (code "38") (name "Net-(U1C--IN)") (class "Default")
      (node (ref "R18") (pin "1") (pinfunction "1_1") (pintype "passive"))
      (node (ref "R19") (pin "2") (pinfunction "2_2") (pintype "passive"))
      (node (ref "U1") (pin "9") (pinfunction "-IN_9") (pintype "input"))
    )
    (net (code "39") (name "Net-(U1D-OUT)") (class "Default")
      (node (ref "LED3_GATE") (pin "A") (pinfunction "A_A") (pintype "passive"))
      (node (ref "U1") (pin "14") (pinfunction "OUT_14") (pintype "output"))
    )
    (net (code "40") (name "Net-(U2A-+IN)") (class "Default")
      (node (ref "C11") (pin "1") (pinfunction "1_1") (pintype "passive"))
      (node (ref "R23") (pin "2") (pinfunction "2_2") (pintype "passive"))
      (node (ref "R24") (pin "2") (pinfunction "2_2") (pintype "passive"))
      (node (ref "R25") (pin "2") (pinfunction "2_2") (pintype "passive"))
      (node (ref "R26") (pin "2") (pinfunction "2_2") (pintype "passive"))
      (node (ref "R27") (pin "2") (pinfunction "2_2") (pintype "passive"))
      (node (ref "R28") (pin "2") (pinfunction "2_2") (pintype "passive"))
      (node (ref "R29") (pin "2") (pinfunction "2_2") (pintype "passive"))
      (node (ref "U2") (pin "3") (pinfunction "+IN_3") (pintype "input"))
    )
    (net (code "41") (name "Net-(U2B-OUT)") (class "Default")
      (node (ref "LED2_ENV") (pin "A") (pinfunction "A_A") (pintype "passive"))
      (node (ref "U2") (pin "7") (pinfunction "OUT_7") (pintype "output"))
    )
    (net (code "42") (name "Net-(U2C--IN)") (class "Default")
      (node (ref "D7") (pin "C") (pinfunction "C_C") (pintype "passive"))
      (node (ref "R32") (pin "2") (pinfunction "2_2") (pintype "passive"))
      (node (ref "R33") (pin "1") (pinfunction "1_1") (pintype "passive"))
      (node (ref "U2") (pin "9") (pinfunction "-IN_9") (pintype "input"))
    )
    (net (code "43") (name "Net-(U2C-OUT)") (class "Default")
      (node (ref "D7") (pin "A") (pinfunction "A_A") (pintype "passive"))
      (node (ref "D8") (pin "C") (pinfunction "C_C") (pintype "passive"))
      (node (ref "U2") (pin "8") (pinfunction "OUT_8") (pintype "output"))
    )
    (net (code "44") (name "Net-(U2D--IN)") (class "Default")
      (node (ref "C14") (pin "1") (pinfunction "1_1") (pintype "passive"))
      (node (ref "R30") (pin "1") (pinfunction "1_1") (pintype "passive"))
      (node (ref "R31") (pin "2") (pinfunction "2_2") (pintype "passive"))
      (node (ref "R34") (pin "2") (pinfunction "2_2") (pintype "passive"))
      (node (ref "R35") (pin "2") (pinfunction "2_2") (pintype "passive"))
      (node (ref "U2") (pin "13") (pinfunction "-IN_13") (pintype "input"))
    )
    (net (code "45") (name "VCC") (class "Default")
      (node (ref "C1") (pin "1") (pinfunction "1_1") (pintype "passive"))
      (node (ref "C13") (pin "1") (pinfunction "1_1") (pintype "passive"))
      (node (ref "C4") (pin "1") (pinfunction "1_1") (pintype "passive"))
      (node (ref "C9") (pin "1") (pinfunction "1_1") (pintype "passive"))
      (node (ref "IC1") (pin "7") (pinfunction "V+_7") (pintype "power_in"))
      (node (ref "L1") (pin "1") (pinfunction "1_1") (pintype "passive"))
      (node (ref "R16") (pin "1") (pinfunction "1_1") (pintype "passive"))
      (node (ref "R18") (pin "2") (pinfunction "2_2") (pintype "passive"))
      (node (ref "U1") (pin "4") (pinfunction "V+_4") (pintype "power_in"))
      (node (ref "U2") (pin "4") (pinfunction "V+_4") (pintype "power_in"))
    )
    (net (code "46") (name "VEE") (class "Default")
      (node (ref "C12") (pin "2") (pinfunction "2_2") (pintype "passive"))
      (node (ref "C2") (pin "2") (pinfunction "2_2") (pintype "passive"))
      (node (ref "C6") (pin "2") (pinfunction "2_2") (pintype "passive"))
      (node (ref "IC1") (pin "4") (pinfunction "V-_4") (pintype "power_in"))
      (node (ref "L2") (pin "1") (pinfunction "1_1") (pintype "passive"))
      (node (ref "R12") (pin "2") (pinfunction "2_2") (pintype "passive"))
      (node (ref "U2") (pin "11") (pinfunction "V-_11") (pintype "power_in"))
    )
    (net (code "47") (name "unconnected-(ENV-2-PadP2)") (class "Default")
      (node (ref "ENV") (pin "P2") (pinfunction "2_P2") (pintype "passive"))
    )
    (net (code "48") (name "unconnected-(GATE-2-PadP2)") (class "Default")
      (node (ref "GATE") (pin "P2") (pinfunction "2_P2") (pintype "passive"))
    )
    (net (code "49") (name "unconnected-(OUT-2-PadP2)") (class "Default")
      (node (ref "OUT") (pin "P2") (pinfunction "2_P2") (pintype "passive"))
    )
    (net (code "50") (name "~{GATE}") (class "Default")
      (node (ref "R15") (pin "1") (pinfunction "1_1") (pintype "passive"))
      (node (ref "R17") (pin "2") (pinfunction "2_2") (pintype "passive"))
      (node (ref "U1") (pin "7") (pinfunction "OUT_7") (pintype "output"))
    )
  )
)
